# TX1.net
KiCad netlist of a schematic drawn in Altium Designer
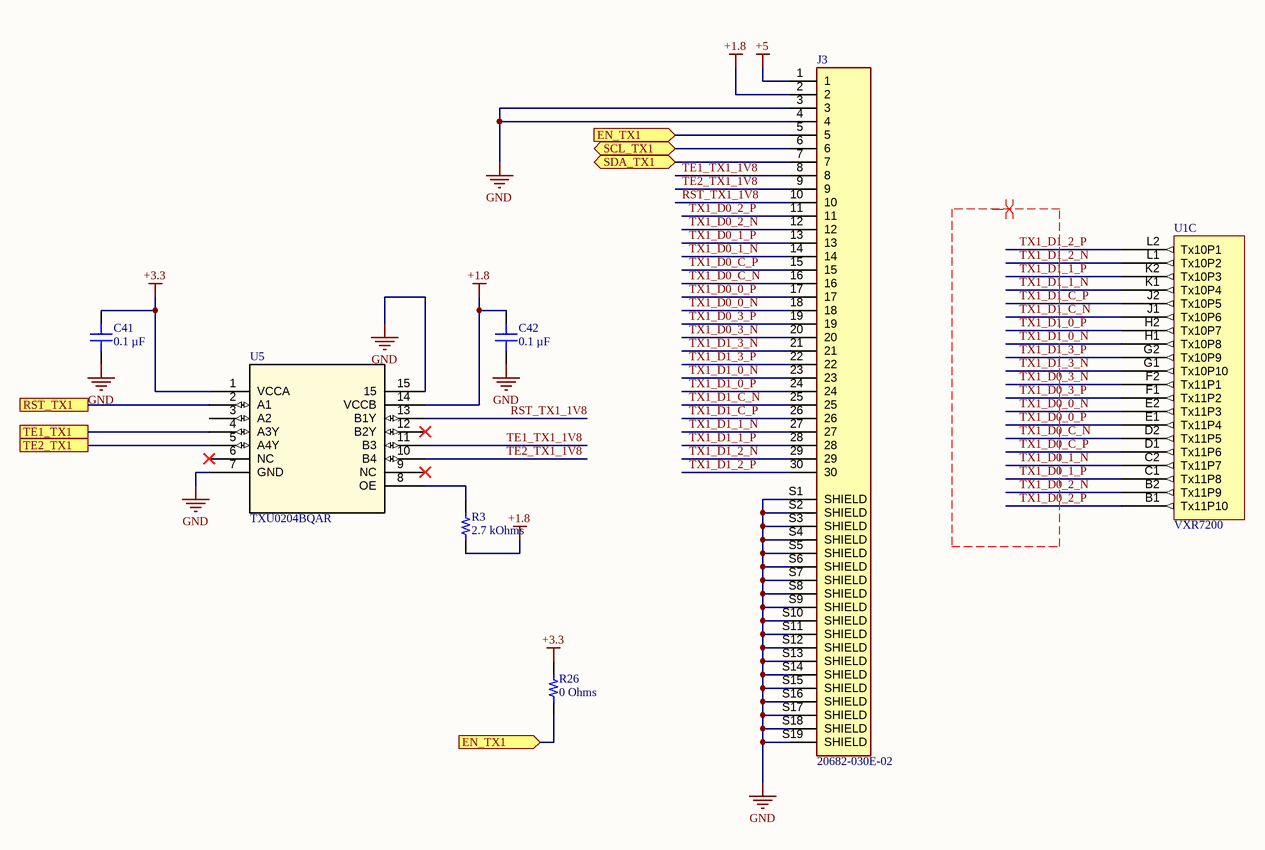
[diagram p0: TX1.SchDoc]

(export (version "E")
  (design (tool "Eeschema 10.0.6"))
  (components
    (comp (ref "C41")
      (value "0.1 µF")
      (footprint "CAP 0201_0603")
      (description "CAP CER 0.1UF 25V X5R 0201")
      (fields
        (field (name "PART NUMBER") "GRM033R61E104KE14D")
        (field (name "MANUFACTURER") "Murata Electronics")
      )
      (libsource (lib "Celestial Altium Library - altium_library") (part "Capacitor"))
    )
    (comp (ref "C42")
      (value "0.1 µF")
      (footprint "CAP 0201_0603")
      (description "CAP CER 0.1UF 25V X5R 0201")
      (fields
        (field (name "PART NUMBER") "GRM033R61E104KE14D")
        (field (name "MANUFACTURER") "Murata Electronics")
      )
      (libsource (lib "Celestial Altium Library - altium_library") (part "Capacitor"))
    )
    (comp (ref "J3")
      (value "20682-030E-02")
      (footprint "20682-030E-02:IPEX_20682-030E-02")
      (description "Cabline-CAII Rece. Ass'y")
      (fields (field (name "MF") "{'manufacturer': u'I-PEX'}"))
      (libsource (lib "*") (part "20682-030E-02"))
    )
    (comp (ref "R3")
      (value "2.7 kOhms")
      (footprint "RES 0201_0603")
      (description "RES 2.7K OHM 5% 1/20W 0201 SMD")
      (fields
        (field (name "PART NUMBER") "ERJ-U01J272C")
        (field (name "MANUFACTURER") "Panasonic Electronic Components")
      )
      (libsource (lib "Celestial Altium Library - altium_library") (part "Resistor"))
    )
    (comp (ref "R26")
      (value "0 Ohms")
      (footprint "RES 0402_1005")
      (description "RESISTOR 0402 JUMPER ZERO OHM")
      (fields (field (name "PART NUMBER") "AC0402FR-070RL") (field (name "MANUFACTURER") "Yageo"))
      (libsource (lib "Celestial Altium Library - altium_library") (part "Resistor"))
    )
    (comp (ref "U1")
      (value "VXR7200")
      (footprint "BGA100P9X9-81A")
      (description "VXR7200 DP to MIPI-DSI bridge")
      (libsource (lib "SimulaVR") (part "VXR7200-Symbol-1"))
    )
    (comp (ref "U5")
      (value "TXU0204BQAR")
      (footprint "WQFN_04BQAR_TEX")
      (description "No Description Available")
      (fields (field (name "COPYRIGHT") "Copyright (C) 2022 Ultra Librarian. All rights reserved."))
      (libsource (lib "SimulaVR") (part "TXU0204BQAR"))
    )
  )
  (nets
    (net (code "1") (name "+1.8") (class "Default")
      (node (ref "C42") (pin "2") (pinfunction "2_2") (pintype "passive"))
      (node (ref "J3") (pin "2") (pinfunction "2_2") (pintype "passive"))
      (node (ref "R3") (pin "1") (pinfunction "1_1") (pintype "passive"))
      (node (ref "U5") (pin "14") (pinfunction "VCCB_14") (pintype "power_in"))
    )
    (net (code "2") (name "+3.3") (class "Default")
      (node (ref "C41") (pin "2") (pinfunction "2_2") (pintype "passive"))
      (node (ref "R26") (pin "2") (pinfunction "2_2") (pintype "passive"))
      (node (ref "U5") (pin "1") (pinfunction "VCCA_1") (pintype "power_in"))
    )
    (net (code "3") (name "+5") (class "Default")
      (node (ref "J3") (pin "1") (pinfunction "1_1") (pintype "passive"))
    )
    (net (code "4") (name "/EN_TX1") (class "Default")
      (node (ref "J3") (pin "5") (pinfunction "5_5") (pintype "passive"))
      (node (ref "R26") (pin "1") (pinfunction "1_1") (pintype "passive"))
    )
    (net (code "5") (name "/RST_TX1") (class "Default")
      (node (ref "U5") (pin "2") (pinfunction "A1_2") (pintype "bidirectional"))
    )
    (net (code "6") (name "/RST_TX1_1V8") (class "Default")
      (node (ref "J3") (pin "10") (pinfunction "10_10") (pintype "passive"))
      (node (ref "U5") (pin "13") (pinfunction "B1Y_13") (pintype "bidirectional"))
    )
    (net (code "7") (name "/SCL_TX1") (class "Default")
      (node (ref "J3") (pin "6") (pinfunction "6_6") (pintype "passive"))
    )
    (net (code "8") (name "/SDA_TX1") (class "Default")
      (node (ref "J3") (pin "7") (pinfunction "7_7") (pintype "passive"))
    )
    (net (code "9") (name "/TE1_TX1") (class "Default")
      (node (ref "U5") (pin "4") (pinfunction "A3Y_4") (pintype "bidirectional"))
    )
    (net (code "10") (name "/TE1_TX1_1V8") (class "Default")
      (node (ref "J3") (pin "8") (pinfunction "8_8") (pintype "passive"))
      (node (ref "U5") (pin "11") (pinfunction "B3_11") (pintype "bidirectional"))
    )
    (net (code "11") (name "/TE2_TX1") (class "Default")
      (node (ref "U5") (pin "5") (pinfunction "A4Y_5") (pintype "bidirectional"))
    )
    (net (code "12") (name "/TE2_TX1_1V8") (class "Default")
      (node (ref "J3") (pin "9") (pinfunction "9_9") (pintype "passive"))
      (node (ref "U5") (pin "10") (pinfunction "B4_10") (pintype "bidirectional"))
    )
    (net (code "13") (name "/TX1_D0_0_N") (class "Default")
      (node (ref "J3") (pin "18") (pinfunction "18_18") (pintype "passive"))
      (node (ref "U1") (pin "E2") (pinfunction "Tx11P3_E2") (pintype "output"))
    )
    (net (code "14") (name "/TX1_D0_0_P") (class "Default")
      (node (ref "J3") (pin "17") (pinfunction "17_17") (pintype "passive"))
      (node (ref "U1") (pin "E1") (pinfunction "Tx11P4_E1") (pintype "output"))
    )
    (net (code "15") (name "/TX1_D0_1_N") (class "Default")
      (node (ref "J3") (pin "14") (pinfunction "14_14") (pintype "passive"))
      (node (ref "U1") (pin "C2") (pinfunction "Tx11P7_C2") (pintype "output"))
    )
    (net (code "16") (name "/TX1_D0_1_P") (class "Default")
      (node (ref "J3") (pin "13") (pinfunction "13_13") (pintype "passive"))
      (node (ref "U1") (pin "C1") (pinfunction "Tx11P8_C1") (pintype "output"))
    )
    (net (code "17") (name "/TX1_D0_2_N") (class "Default")
      (node (ref "J3") (pin "12") (pinfunction "12_12") (pintype "passive"))
      (node (ref "U1") (pin "B2") (pinfunction "Tx11P9_B2") (pintype "output"))
    )
    (net (code "18") (name "/TX1_D0_2_P") (class "Default")
      (node (ref "J3") (pin "11") (pinfunction "11_11") (pintype "passive"))
      (node (ref "U1") (pin "B1") (pinfunction "Tx11P10_B1") (pintype "output"))
    )
    (net (code "19") (name "/TX1_D0_3_N") (class "Default")
      (node (ref "J3") (pin "20") (pinfunction "20_20") (pintype "passive"))
      (node (ref "U1") (pin "F2") (pinfunction "Tx11P1_F2") (pintype "output"))
    )
    (net (code "20") (name "/TX1_D0_3_P") (class "Default")
      (node (ref "J3") (pin "19") (pinfunction "19_19") (pintype "passive"))
      (node (ref "U1") (pin "F1") (pinfunction "Tx11P2_F1") (pintype "output"))
    )
    (net (code "21") (name "/TX1_D0_C_N") (class "Default")
      (node (ref "J3") (pin "16") (pinfunction "16_16") (pintype "passive"))
      (node (ref "U1") (pin "D2") (pinfunction "Tx11P5_D2") (pintype "output"))
    )
    (net (code "22") (name "/TX1_D0_C_P") (class "Default")
      (node (ref "J3") (pin "15") (pinfunction "15_15") (pintype "passive"))
      (node (ref "U1") (pin "D1") (pinfunction "Tx11P6_D1") (pintype "output"))
    )
    (net (code "23") (name "/TX1_D1_0_N") (class "Default")
      (node (ref "J3") (pin "23") (pinfunction "23_23") (pintype "passive"))
      (node (ref "U1") (pin "H1") (pinfunction "Tx10P8_H1") (pintype "output"))
    )
    (net (code "24") (name "/TX1_D1_0_P") (class "Default")
      (node (ref "J3") (pin "24") (pinfunction "24_24") (pintype "passive"))
      (node (ref "U1") (pin "H2") (pinfunction "Tx10P7_H2") (pintype "output"))
    )
    (net (code "25") (name "/TX1_D1_1_N") (class "Default")
      (node (ref "J3") (pin "27") (pinfunction "27_27") (pintype "passive"))
      (node (ref "U1") (pin "K1") (pinfunction "Tx10P4_K1") (pintype "output"))
    )
    (net (code "26") (name "/TX1_D1_1_P") (class "Default")
      (node (ref "J3") (pin "28") (pinfunction "28_28") (pintype "passive"))
      (node (ref "U1") (pin "K2") (pinfunction "Tx10P3_K2") (pintype "output"))
    )
    (net (code "27") (name "/TX1_D1_2_N") (class "Default")
      (node (ref "J3") (pin "29") (pinfunction "29_29") (pintype "passive"))
      (node (ref "U1") (pin "L1") (pinfunction "Tx10P2_L1") (pintype "output"))
    )
    (net (code "28") (name "/TX1_D1_2_P") (class "Default")
      (node (ref "J3") (pin "30") (pinfunction "30_30") (pintype "passive"))
      (node (ref "U1") (pin "L2") (pinfunction "Tx10P1_L2") (pintype "output"))
    )
    (net (code "29") (name "/TX1_D1_3_N") (class "Default")
      (node (ref "J3") (pin "21") (pinfunction "21_21") (pintype "passive"))
      (node (ref "U1") (pin "G1") (pinfunction "Tx10P10_G1") (pintype "output"))
    )
    (net (code "30") (name "/TX1_D1_3_P") (class "Default")
      (node (ref "J3") (pin "22") (pinfunction "22_22") (pintype "passive"))
      (node (ref "U1") (pin "G2") (pinfunction "Tx10P9_G2") (pintype "output"))
    )
    (net (code "31") (name "/TX1_D1_C_N") (class "Default")
      (node (ref "J3") (pin "25") (pinfunction "25_25") (pintype "passive"))
      (node (ref "U1") (pin "J1") (pinfunction "Tx10P6_J1") (pintype "output"))
    )
    (net (code "32") (name "/TX1_D1_C_P") (class "Default")
      (node (ref "J3") (pin "26") (pinfunction "26_26") (pintype "passive"))
      (node (ref "U1") (pin "J2") (pinfunction "Tx10P5_J2") (pintype "output"))
    )
    (net (code "33") (name "GND") (class "Default")
      (node (ref "C41") (pin "1") (pinfunction "1_1") (pintype "passive"))
      (node (ref "C42") (pin "1") (pinfunction "1_1") (pintype "passive"))
      (node (ref "J3") (pin "3") (pinfunction "3_3") (pintype "passive"))
      (node (ref "J3") (pin "4") (pinfunction "4_4") (pintype "passive"))
      (node (ref "J3") (pin "S1") (pinfunction "SHIELD_S1") (pintype "passive"))
      (node (ref "J3") (pin "S10") (pinfunction "SHIELD_S10") (pintype "passive"))
      (node (ref "J3") (pin "S11") (pinfunction "SHIELD_S11") (pintype "passive"))
      (node (ref "J3") (pin "S12") (pinfunction "SHIELD_S12") (pintype "passive"))
      (node (ref "J3") (pin "S13") (pinfunction "SHIELD_S13") (pintype "passive"))
      (node (ref "J3") (pin "S14") (pinfunction "SHIELD_S14") (pintype "passive"))
      (node (ref "J3") (pin "S15") (pinfunction "SHIELD_S15") (pintype "passive"))
      (node (ref "J3") (pin "S16") (pinfunction "SHIELD_S16") (pintype "passive"))
      (node (ref "J3") (pin "S17") (pinfunction "SHIELD_S17") (pintype "passive"))
      (node (ref "J3") (pin "S18") (pinfunction "SHIELD_S18") (pintype "passive"))
      (node (ref "J3") (pin "S19") (pinfunction "SHIELD_S19") (pintype "passive"))
      (node (ref "J3") (pin "S2") (pinfunction "SHIELD_S2") (pintype "passive"))
      (node (ref "J3") (pin "S3") (pinfunction "SHIELD_S3") (pintype "passive"))
      (node (ref "J3") (pin "S4") (pinfunction "SHIELD_S4") (pintype "passive"))
      (node (ref "J3") (pin "S5") (pinfunction "SHIELD_S5") (pintype "passive"))
      (node (ref "J3") (pin "S6") (pinfunction "SHIELD_S6") (pintype "passive"))
      (node (ref "J3") (pin "S7") (pinfunction "SHIELD_S7") (pintype "passive"))
      (node (ref "J3") (pin "S8") (pinfunction "SHIELD_S8") (pintype "passive"))
      (node (ref "J3") (pin "S9") (pinfunction "SHIELD_S9") (pintype "passive"))
      (node (ref "U5") (pin "15") (pinfunction "15_15") (pintype "passive"))
      (node (ref "U5") (pin "7") (pinfunction "GND_7") (pintype "passive"))
    )
    (net (code "34") (name "Net-(U5-OE)") (class "Default")
      (node (ref "R3") (pin "2") (pinfunction "2_2") (pintype "passive"))
      (node (ref "U5") (pin "8") (pinfunction "OE_8") (pintype "passive"))
    )
    (net (code "35") (name "unconnected-(U5-A2-Pad3)") (class "Default")
      (node (ref "U5") (pin "3") (pinfunction "A2_3") (pintype "bidirectional"))
    )
    (net (code "36") (name "unconnected-(U5-B2Y-Pad12)") (class "Default")
      (node (ref "U5") (pin "12") (pinfunction "B2Y_12") (pintype "bidirectional+no_connect"))
    )
    (net (code "37") (name "unconnected-(U5-NC-Pad6)") (class "Default")
      (node (ref "U5") (pin "6") (pinfunction "NC_6") (pintype "passive+no_connect"))
    )
    (net (code "38") (name "unconnected-(U5-NC-Pad9)") (class "Default")
      (node (ref "U5") (pin "9") (pinfunction "NC_9") (pintype "passive+no_connect"))
    )
  )
)
